# Carte_Alim_TOP.net
KiCad netlist of a schematic drawn in Altium Designer
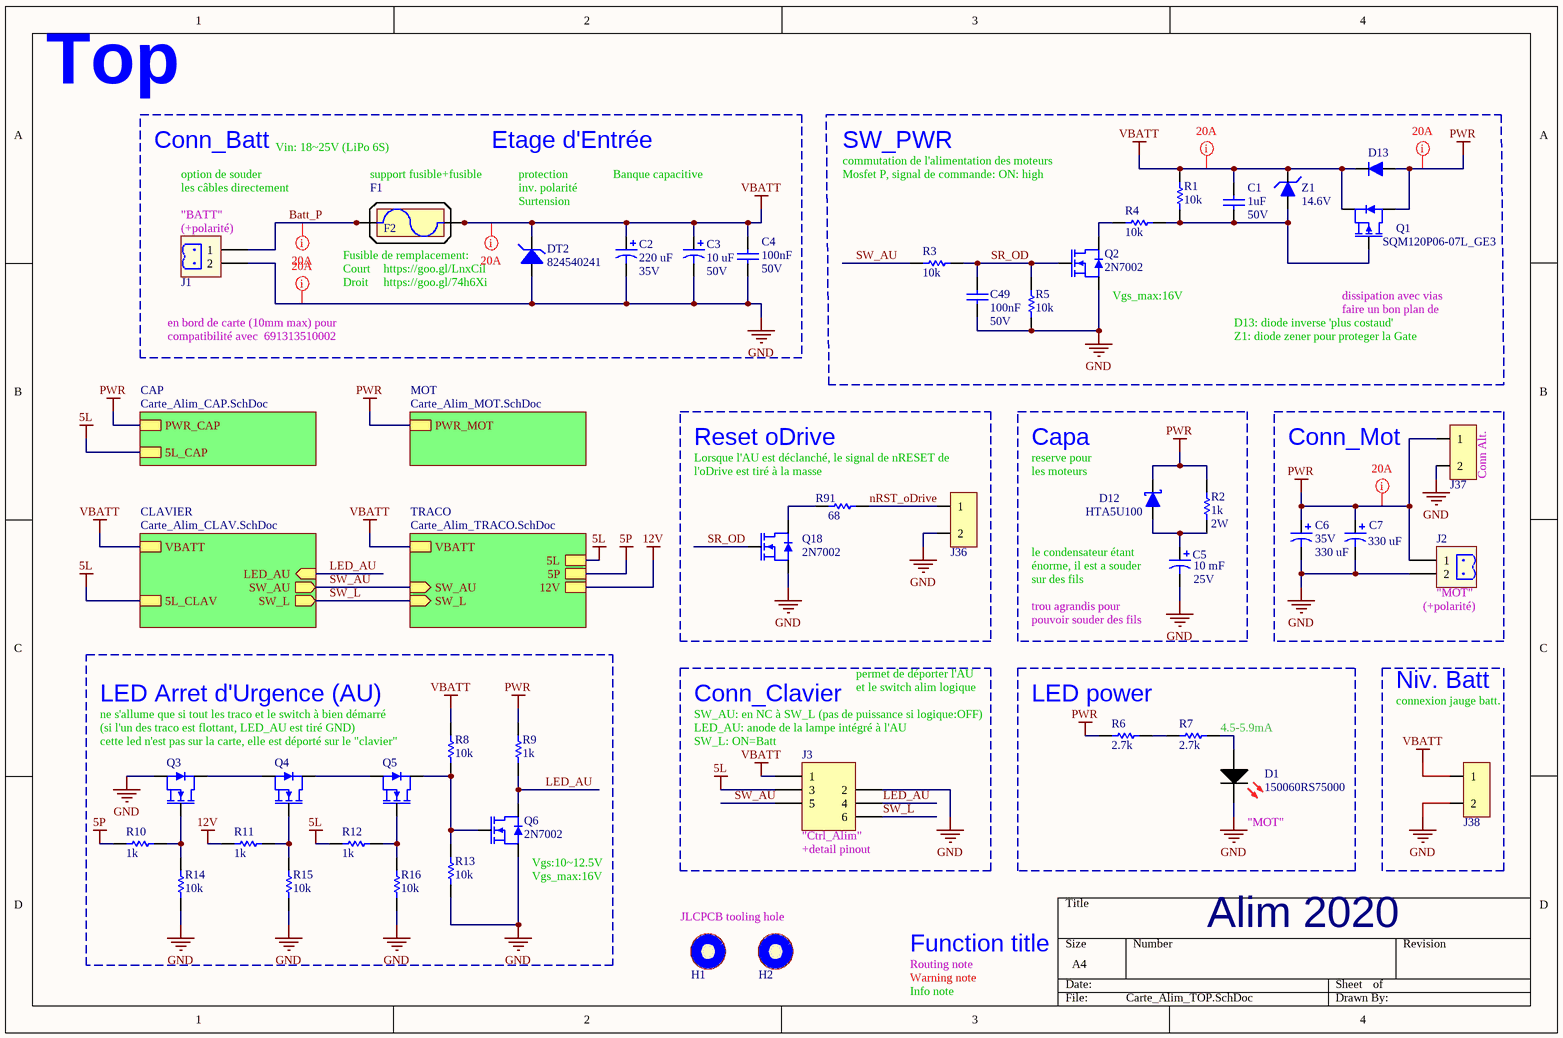
[diagram p0: Carte_Alim_TOP.SchDoc]

(export (version "E")
  (design (tool "Eeschema 10.0.6"))
  (components
    (comp (ref "C1")
      (value "1uF")
      (footprint "WCAP-CSGP_0805, 2x1.25x1.25")
      (description "CAP CER 1uF 50V X7R 0805")
      (fields
        (field (name "MANUFACTURER") "Wurth Elektronik")
        (field (name "MANUFACTURER PART NUMBER") "885012207103")
        (field (name "RATEDVOLTAGE") "50V")
      )
      (libsource (lib "Condensateur") (part "WCAP-CSGP, 885012207103"))
    )
    (comp (ref "C2")
      (value "220 uF")
      (footprint "WCAP-ATG8_8x11.5x3.5x0.5")
      (description "CAP Alu 220 UF 20% 35 V")
      (fields
        (field (name "MANUFACTURER") "Wurth Elektronik")
        (field (name "MANUFACTURER PART NUMBER") "860010574011")
        (field (name "RATEDVOLTAGE") "35V")
      )
      (libsource (lib "Condensateur") (part "WCAP-ATG8, 860010574011"))
    )
    (comp (ref "C3")
      (value "10 uF")
      (footprint "WCAP-ATG8_5x11x2x0.5")
      (description "CAP Alu 10 UF 20% 50 V")
      (fields
        (field (name "RATEDVOLTAGE") "50V")
        (field (name "MANUFACTURER") "Wurth Elektronik")
        (field (name "MANUFACTURER PART NUMBER") "860010672009")
      )
      (libsource (lib "Condensateur") (part "WCAP-ATG8, 860010672009"))
    )
    (comp (ref "C4")
      (value "100nF")
      (footprint "WCAP-CSGP_0603, 1.6x0.8x0.8")
      (description "CAP CER 100nF 50V X7R 0603")
      (fields
        (field (name "RATEDVOLTAGE") "50V")
        (field (name "MANUFACTURER") "Wurth Elektronik")
        (field (name "MANUFACTURER PART NUMBER") "885012206095")
      )
      (libsource (lib "Condensateur") (part "WCAP-CSGP, 885012206095"))
    )
    (comp (ref "C5")
      (value "10 mF")
      (footprint "WCAP-ATG8_22x41x10x0.8")
      (description "CAP Alu 10'000 UF 25 V")
      (fields
        (field (name "MANUFACTURER PART NUMBER") "860010483029")
        (field (name "MANUFACTURER") "Wurth Elektronik")
        (field (name "RATEDVOLTAGE") "25V")
      )
      (libsource (lib "Condensateur") (part "WCAP-ATG8, 860010483029"))
    )
    (comp (ref "C6")
      (value "330 uF")
      (footprint "WCAP-ATG8_10x12.5x5x0.6")
      (description "CAP Alu 330 UF 20% 35 V")
      (fields
        (field (name "MANUFACTURER") "Wurth Elektronik")
        (field (name "MANUFACTURER PART NUMBER") "860010575012")
        (field (name "RATEDVOLTAGE") "35V")
      )
      (libsource (lib "Condensateur") (part "WCAP-ATG8, 860010575012"))
    )
    (comp (ref "C7")
      (value "330 uF")
      (footprint "WCAP-ATG8_10x12.5x5x0.6")
      (description "CAP Alu 330 UF 20% 35 V")
      (fields
        (field (name "MANUFACTURER") "Wurth Elektronik")
        (field (name "MANUFACTURER PART NUMBER") "860010575012")
      )
      (libsource (lib "Condensateur") (part "WCAP-ATG8, 860010575012"))
    )
    (comp (ref "C49")
      (value "100nF")
      (footprint "WCAP-CSGP_0603, 1.6x0.8x0.8")
      (description "CAP CER 100nF 50V X7R 0603")
      (fields
        (field (name "RATEDVOLTAGE") "50V")
        (field (name "MANUFACTURER") "Wurth Elektronik")
        (field (name "MANUFACTURER PART NUMBER") "885012206095")
      )
      (libsource (lib "Condensateur") (part "WCAP-CSGP, 885012206095"))
    )
    (comp (ref "D1")
      (value "150060RS75000")
      (footprint "SMCW_0603")
      (description "SMD mono-color Chip LED, WL-SMCW, Red")
      (fields (field (name "MANUFACTURER") "Wurth Elektronik"))
      (libsource (lib "Opto") (part "WL-SMCW 0603  150060RS75000"))
    )
    (comp (ref "D12")
      (value "HTA5U100")
      (footprint "SMA, DO-214AC")
      (description "DIODE SCHOTTKY 100V 5A SMA (DO-214AC)")
      (fields (field (name "MANUFACTURER") "MULTICOMP"))
      (libsource (lib "Diode") (part "HTA5U100"))
    )
    (comp (ref "D13")
      (value "RS3J R6")
      (footprint "SMC, DO-214AB")
      (description "DIODE GEN PURP 600V 3A SMC")
      (fields (field (name "MANUFACTURER") "TAIWAN SEMICONDUCTOR"))
      (libsource (lib "Diode") (part "RS3J_R6"))
    )
    (comp (ref "DT2")
      (value "824540241")
      (footprint "SMC, DO-214AB")
      (description "WE-TVSP Power TVS Diode, Unidirectional, 1500 W, 24 VDC")
      (fields (field (name "MANUFACTURER") "Wurth Electronics Inc."))
      (libsource (lib "Diode") (part "824540241"))
    )
    (comp (ref "F1")
      (value "3557-2")
      (footprint "3557-2")
      (description "FUSE Holder 500V 30A PCB")
      (fields (field (name "MANUFACTURER") "Keystone Electronics"))
      (libsource (lib "Fuse") (part "3557-2"))
    )
    (comp (ref "F2")
      (value "0891030.NXS")
      (description "FUSE AUTO 30A 58VDC BLADE MINI")
      (fields (field (name "MANUFACTURER") "Littelfuse Inc."))
      (libsource (lib "Fuse") (part "0891030.NXS"))
    )
    (comp (ref "H1")
      (value "1.152mm")
      (footprint "Tooling_hole_JLCPCB")
      (description "Tooling hole pour JLCPCB assembly")
      (libsource (lib "Divers") (part "HOLE_TOOLING"))
    )
    (comp (ref "H2")
      (value "1.152mm")
      (footprint "Tooling_hole_JLCPCB")
      (description "Tooling hole pour JLCPCB assembly")
      (libsource (lib "Divers") (part "HOLE_TOOLING"))
    )
    (comp (ref "J1")
      (value "691311500102")
      (footprint "691311500102")
      (description "WR-TBL 2p Series 311 - 5.08 mm Closed Vertical PCB Header")
      (fields (field (name "MANUFACTURER") "Wurth Electronics Inc."))
      (libsource (lib "Connecteurs") (part "691311500102"))
    )
    (comp (ref "J2")
      (value "691311500102")
      (footprint "691311500102")
      (description "WR-TBL 2p Series 311 - 5.08 mm Closed Vertical PCB Header")
      (fields (field (name "MANUFACTURER") "Wurth Electronics Inc."))
      (libsource (lib "") (part "691311500102_1"))
    )
    (comp (ref "J3")
      (value "690367280676")
      (footprint "690367280676")
      (description "WR-MM 6p Female SMT Connector with Polarization")
      (fields (field (name "MANUFACTURER") "Wurth Electronics Inc."))
      (libsource (lib "Connecteurs") (part "690367280676"))
    )
    (comp (ref "J36")
      (value "22-03-2021")
      (footprint "22-03-2021")
      (description "CONN HEADER VERT 2POS 2.54MM")
      (fields (field (name "MANUFACTURER") "MOLEX"))
      (libsource (lib "Connecteurs") (part "22-03-2021"))
    )
    (comp (ref "J37")
      (value "22-03-2021")
      (footprint "22-03-2021")
      (description "CONN HEADER VERT 2POS 2.54MM")
      (fields (field (name "MANUFACTURER") "MOLEX"))
      (libsource (lib "Connecteurs") (part "22-03-2021"))
    )
    (comp (ref "J38")
      (value "22-03-2021")
      (footprint "22-03-2021")
      (description "CONN HEADER VERT 2POS 2.54MM")
      (fields (field (name "MANUFACTURER") "MOLEX"))
      (libsource (lib "Connecteurs") (part "22-03-2021"))
    )
    (comp (ref "Q1")
      (value "SQM120P06-07L_GE3")
      (footprint "TO263AB, D2PAK")
      (description "MOSFET P 60V 120A D2PAK")
      (fields (field (name "MANUFACTURER") "VISHAY"))
      (libsource (lib "Transistors") (part "SQM120P06-07L_GE3"))
    )
    (comp (ref "Q2")
      (value "2N7002")
      (footprint "SOT-23")
      (description "MOSFET N 60V 115MA SOT23")
      (fields (field (name "MANUFACTURER") "Changjiang Electronics Tech (CJ)"))
      (libsource (lib "Transistors") (part "2N7002"))
    )
    (comp (ref "Q3")
      (value "2N7002")
      (footprint "SOT-23")
      (description "MOSFET N 60V 115MA SOT23")
      (fields (field (name "MANUFACTURER") "Changjiang Electronics Tech (CJ)"))
      (libsource (lib "Transistors") (part "2N7002"))
    )
    (comp (ref "Q4")
      (value "2N7002")
      (footprint "SOT-23")
      (description "MOSFET N 60V 115MA SOT23")
      (fields (field (name "MANUFACTURER") "Changjiang Electronics Tech (CJ)"))
      (libsource (lib "Transistors") (part "2N7002"))
    )
    (comp (ref "Q5")
      (value "2N7002")
      (footprint "SOT-23")
      (description "MOSFET N 60V 115MA SOT23")
      (fields (field (name "MANUFACTURER") "Changjiang Electronics Tech (CJ)"))
      (libsource (lib "Transistors") (part "2N7002"))
    )
    (comp (ref "Q6")
      (value "2N7002")
      (footprint "SOT-23")
      (description "MOSFET N 60V 115MA SOT23")
      (fields (field (name "MANUFACTURER") "Changjiang Electronics Tech (CJ)"))
      (libsource (lib "Transistors") (part "2N7002"))
    )
    (comp (ref "Q18")
      (value "2N7002")
      (footprint "SOT-23")
      (description "MOSFET N 60V 115MA SOT23")
      (fields (field (name "MANUFACTURER") "Changjiang Electronics Tech (CJ)"))
      (libsource (lib "Transistors") (part "2N7002"))
    )
    (comp (ref "R1")
      (value "10k")
      (footprint "RESC1608X06N")
      (description "RES SMD 10K OHM 1% 1/10W 0603")
      (fields
        (field (name "MANUFACTURER") "Yageo")
        (field (name "MANUFACTURER PART NUMBER") "RC0603FR-0710KL")
      )
      (libsource (lib "Resistance") (part "RC0603FR-0710KL"))
    )
    (comp (ref "R2")
      (value "1k")
      (footprint "RESADV480W80L1200D390")
      (description "resistance traversante verticale générique")
      (fields
        (field (name "MANUFACTURER") "MULTICOMP")
        (field (name "MANUFACTURER PART NUMBER") "MCKNP02WJ0102A19")
        (field (name "POWER") "2W")
      )
      (libsource (lib "Resistance") (part "Generic_TH_Vert_Res"))
    )
    (comp (ref "R3")
      (value "10k")
      (footprint "RESC1608X06N")
      (description "RES SMD 10K OHM 1% 1/10W 0603")
      (fields
        (field (name "MANUFACTURER") "Yageo")
        (field (name "MANUFACTURER PART NUMBER") "RC0603FR-0710KL")
      )
      (libsource (lib "Resistance") (part "RC0603FR-0710KL"))
    )
    (comp (ref "R4")
      (value "10k")
      (footprint "RESC1608X06N")
      (description "RES SMD 10K OHM 1% 1/10W 0603")
      (fields
        (field (name "MANUFACTURER") "Yageo")
        (field (name "MANUFACTURER PART NUMBER") "RC0603FR-0710KL")
      )
      (libsource (lib "Resistance") (part "RC0603FR-0710KL"))
    )
    (comp (ref "R5")
      (value "10k")
      (footprint "RESC1608X06N")
      (description "RES SMD 10K OHM 1% 1/10W 0603")
      (fields
        (field (name "MANUFACTURER") "Yageo")
        (field (name "MANUFACTURER PART NUMBER") "RC0603FR-0710KL")
      )
      (libsource (lib "Resistance") (part "RC0603FR-0710KL"))
    )
    (comp (ref "R6")
      (value "2.7k")
      (footprint "RESC2012X06N")
      (description "RES SMD 2K7 OHM 1% 1/8W 0805")
      (fields
        (field (name "MANUFACTURER") "Yageo")
        (field (name "MANUFACTURER PART NUMBER") "RC0805FR-072K7L")
      )
      (libsource (lib "Resistance") (part "RC0805FR-072K7L"))
    )
    (comp (ref "R7")
      (value "2.7k")
      (footprint "RESC2012X06N")
      (description "RES SMD 2K7 OHM 1% 1/8W 0805")
      (fields
        (field (name "MANUFACTURER") "Yageo")
        (field (name "MANUFACTURER PART NUMBER") "RC0805FR-072K7L")
      )
      (libsource (lib "Resistance") (part "RC0805FR-072K7L"))
    )
    (comp (ref "R8")
      (value "10k")
      (footprint "RESC1608X06N")
      (description "RES SMD 10K OHM 1% 1/10W 0603")
      (fields
        (field (name "MANUFACTURER") "Yageo")
        (field (name "MANUFACTURER PART NUMBER") "RC0603FR-0710KL")
      )
      (libsource (lib "Resistance") (part "RC0603FR-0710KL"))
    )
    (comp (ref "R9")
      (value "1k")
      (footprint "RESC1608X06N")
      (description "RES SMD 1K OHM 1% 1/10W 0603")
      (fields
        (field (name "MANUFACTURER") "Yageo")
        (field (name "MANUFACTURER PART NUMBER") "RC0603FR-071KL")
      )
      (libsource (lib "Resistance") (part "RC0603FR-071KL"))
    )
    (comp (ref "R10")
      (value "1k")
      (footprint "RESC1608X06N")
      (description "RES SMD 1K OHM 1% 1/10W 0603")
      (fields
        (field (name "MANUFACTURER") "Yageo")
        (field (name "MANUFACTURER PART NUMBER") "RC0603FR-071KL")
      )
      (libsource (lib "Resistance") (part "RC0603FR-071KL"))
    )
    (comp (ref "R11")
      (value "1k")
      (footprint "RESC1608X06N")
      (description "RES SMD 1K OHM 1% 1/10W 0603")
      (fields
        (field (name "MANUFACTURER") "Yageo")
        (field (name "MANUFACTURER PART NUMBER") "RC0603FR-071KL")
      )
      (libsource (lib "Resistance") (part "RC0603FR-071KL"))
    )
    (comp (ref "R12")
      (value "1k")
      (footprint "RESC1608X06N")
      (description "RES SMD 1K OHM 1% 1/10W 0603")
      (fields
        (field (name "MANUFACTURER") "Yageo")
        (field (name "MANUFACTURER PART NUMBER") "RC0603FR-071KL")
      )
      (libsource (lib "Resistance") (part "RC0603FR-071KL"))
    )
    (comp (ref "R13")
      (value "10k")
      (footprint "RESC1608X06N")
      (description "RES SMD 10K OHM 1% 1/10W 0603")
      (fields
        (field (name "MANUFACTURER") "Yageo")
        (field (name "MANUFACTURER PART NUMBER") "RC0603FR-0710KL")
      )
      (libsource (lib "Resistance") (part "RC0603FR-0710KL"))
    )
    (comp (ref "R14")
      (value "10k")
      (footprint "RESC1608X06N")
      (description "RES SMD 10K OHM 1% 1/10W 0603")
      (fields
        (field (name "MANUFACTURER") "Yageo")
        (field (name "MANUFACTURER PART NUMBER") "RC0603FR-0710KL")
      )
      (libsource (lib "Resistance") (part "RC0603FR-0710KL"))
    )
    (comp (ref "R15")
      (value "10k")
      (footprint "RESC1608X06N")
      (description "RES SMD 10K OHM 1% 1/10W 0603")
      (fields
        (field (name "MANUFACTURER") "Yageo")
        (field (name "MANUFACTURER PART NUMBER") "RC0603FR-0710KL")
      )
      (libsource (lib "Resistance") (part "RC0603FR-0710KL"))
    )
    (comp (ref "R16")
      (value "10k")
      (footprint "RESC1608X06N")
      (description "RES SMD 10K OHM 1% 1/10W 0603")
      (fields
        (field (name "MANUFACTURER") "Yageo")
        (field (name "MANUFACTURER PART NUMBER") "RC0603FR-0710KL")
      )
      (libsource (lib "Resistance") (part "RC0603FR-0710KL"))
    )
    (comp (ref "R91")
      (value "68")
      (footprint "RESC1608X06N")
      (description "RES SMD 68 OHM 1% 1/10W 0603")
      (fields
        (field (name "MANUFACTURER") "Yageo")
        (field (name "MANUFACTURER PART NUMBER") "RC0603FR-0768RL")
      )
      (libsource (lib "Resistance") (part "RC0603FR-0768RL"))
    )
    (comp (ref "Z1")
      (value "14.6V")
      (footprint "SOD-323")
      (description "DIODE ZENER 14.6V 300mW SOD323")
      (fields
        (field (name "MANUFACTURER") "ON Semiconductor")
        (field (name "MANUFACTURER PART NUMBER") "MM3Z15VST1G")
      )
      (libsource (lib "Diode") (part "MM3Z15VST1G"))
    )
  )
  (nets
    (net (code "1") (name "/Batt_P") (class "Default")
      (node (ref "F1") (pin "1") (pinfunction "1_1") (pintype "passive"))
      (node (ref "F1") (pin "3") (pinfunction "3_3") (pintype "passive"))
      (node (ref "J1") (pin "1") (pinfunction "1_1") (pintype "passive"))
    )
    (net (code "2") (name "/LED_AU") (class "Default")
      (node (ref "J3") (pin "4") (pinfunction "4_4") (pintype "passive"))
      (node (ref "Q6") (pin "3") (pinfunction "D_3") (pintype "passive"))
      (node (ref "R9") (pin "1") (pinfunction "1_1") (pintype "passive"))
    )
    (net (code "3") (name "/SR_OD") (class "Default")
      (node (ref "C49") (pin "2") (pinfunction "2_2") (pintype "passive"))
      (node (ref "Q18") (pin "1") (pinfunction "G_1") (pintype "passive"))
      (node (ref "Q2") (pin "1") (pinfunction "G_1") (pintype "passive"))
      (node (ref "R3") (pin "2") (pinfunction "2_2") (pintype "passive"))
      (node (ref "R5") (pin "1") (pinfunction "1_1") (pintype "passive"))
    )
    (net (code "4") (name "/SW_AU") (class "Default")
      (node (ref "J3") (pin "5") (pinfunction "5_5") (pintype "passive"))
      (node (ref "R3") (pin "1") (pinfunction "1_1") (pintype "passive"))
    )
    (net (code "5") (name "/SW_L") (class "Default")
      (node (ref "J3") (pin "6") (pinfunction "6_6") (pintype "passive"))
    )
    (net (code "6") (name "/nRST_oDrive") (class "Default")
      (node (ref "J36") (pin "1") (pinfunction "1_1") (pintype "passive"))
      (node (ref "R91") (pin "2") (pinfunction "2_2") (pintype "passive"))
    )
    (net (code "7") (name "5L") (class "Default")
      (node (ref "J3") (pin "3") (pinfunction "3_3") (pintype "passive"))
      (node (ref "R12") (pin "2") (pinfunction "2_2") (pintype "passive"))
    )
    (net (code "8") (name "5P") (class "Default")
      (node (ref "R10") (pin "2") (pinfunction "2_2") (pintype "passive"))
    )
    (net (code "9") (name "12V") (class "Default")
      (node (ref "R11") (pin "2") (pinfunction "2_2") (pintype "passive"))
    )
    (net (code "10") (name "GND") (class "Default")
      (node (ref "C2") (pin "2") (pinfunction "2_2") (pintype "passive"))
      (node (ref "C3") (pin "2") (pinfunction "2_2") (pintype "passive"))
      (node (ref "C4") (pin "1") (pinfunction "1_1") (pintype "passive"))
      (node (ref "C49") (pin "1") (pinfunction "1_1") (pintype "passive"))
      (node (ref "C5") (pin "2") (pinfunction "2_2") (pintype "passive"))
      (node (ref "C6") (pin "2") (pinfunction "2_2") (pintype "passive"))
      (node (ref "C7") (pin "2") (pinfunction "2_2") (pintype "passive"))
      (node (ref "D1") (pin "1") (pinfunction "C_1") (pintype "passive"))
      (node (ref "DT2") (pin "1") (pintype "passive"))
      (node (ref "J1") (pin "2") (pinfunction "2_2") (pintype "passive"))
      (node (ref "J2") (pin "2") (pinfunction "2_2") (pintype "passive"))
      (node (ref "J3") (pin "2") (pinfunction "2_2") (pintype "passive"))
      (node (ref "J36") (pin "2") (pinfunction "2_2") (pintype "passive"))
      (node (ref "J37") (pin "2") (pinfunction "2_2") (pintype "passive"))
      (node (ref "J38") (pin "2") (pinfunction "2_2") (pintype "passive"))
      (node (ref "Q18") (pin "2") (pinfunction "S_2") (pintype "passive"))
      (node (ref "Q2") (pin "2") (pinfunction "S_2") (pintype "passive"))
      (node (ref "Q3") (pin "2") (pinfunction "S_2") (pintype "passive"))
      (node (ref "Q6") (pin "2") (pinfunction "S_2") (pintype "passive"))
      (node (ref "R13") (pin "1") (pinfunction "1_1") (pintype "passive"))
      (node (ref "R14") (pin "1") (pinfunction "1_1") (pintype "passive"))
      (node (ref "R15") (pin "1") (pinfunction "1_1") (pintype "passive"))
      (node (ref "R16") (pin "1") (pinfunction "1_1") (pintype "passive"))
      (node (ref "R5") (pin "2") (pinfunction "2_2") (pintype "passive"))
    )
    (net (code "11") (name "Net-(C5-Pad1)") (class "Default")
      (node (ref "C5") (pin "1") (pinfunction "1_1") (pintype "passive"))
      (node (ref "D12") (pin "1") (pintype "passive"))
      (node (ref "R2") (pin "2") (pinfunction "2_2") (pintype "passive"))
    )
    (net (code "12") (name "Net-(D1-A)") (class "Default")
      (node (ref "D1") (pin "2") (pinfunction "A_2") (pintype "passive"))
      (node (ref "R7") (pin "1") (pinfunction "1_1") (pintype "passive"))
    )
    (net (code "13") (name "Net-(Q1-G)") (class "Default")
      (node (ref "C1") (pin "1") (pinfunction "1_1") (pintype "passive"))
      (node (ref "Q1") (pin "1") (pinfunction "G_1") (pintype "passive"))
      (node (ref "R1") (pin "1") (pinfunction "1_1") (pintype "passive"))
      (node (ref "R4") (pin "1") (pinfunction "1_1") (pintype "passive"))
      (node (ref "Z1") (pin "1") (pintype "passive"))
    )
    (net (code "14") (name "Net-(Q2-D)") (class "Default")
      (node (ref "Q2") (pin "3") (pinfunction "D_3") (pintype "passive"))
      (node (ref "R4") (pin "2") (pinfunction "2_2") (pintype "passive"))
    )
    (net (code "15") (name "Net-(Q3-D)") (class "Default")
      (node (ref "Q3") (pin "3") (pinfunction "D_3") (pintype "passive"))
      (node (ref "Q4") (pin "2") (pinfunction "S_2") (pintype "passive"))
    )
    (net (code "16") (name "Net-(Q3-G)") (class "Default")
      (node (ref "Q3") (pin "1") (pinfunction "G_1") (pintype "passive"))
      (node (ref "R10") (pin "1") (pinfunction "1_1") (pintype "passive"))
      (node (ref "R14") (pin "2") (pinfunction "2_2") (pintype "passive"))
    )
    (net (code "17") (name "Net-(Q4-D)") (class "Default")
      (node (ref "Q4") (pin "3") (pinfunction "D_3") (pintype "passive"))
      (node (ref "Q5") (pin "2") (pinfunction "S_2") (pintype "passive"))
    )
    (net (code "18") (name "Net-(Q4-G)") (class "Default")
      (node (ref "Q4") (pin "1") (pinfunction "G_1") (pintype "passive"))
      (node (ref "R11") (pin "1") (pinfunction "1_1") (pintype "passive"))
      (node (ref "R15") (pin "2") (pinfunction "2_2") (pintype "passive"))
    )
    (net (code "19") (name "Net-(Q5-D)") (class "Default")
      (node (ref "Q5") (pin "3") (pinfunction "D_3") (pintype "passive"))
      (node (ref "Q6") (pin "1") (pinfunction "G_1") (pintype "passive"))
      (node (ref "R13") (pin "2") (pinfunction "2_2") (pintype "passive"))
      (node (ref "R8") (pin "1") (pinfunction "1_1") (pintype "passive"))
    )
    (net (code "20") (name "Net-(Q5-G)") (class "Default")
      (node (ref "Q5") (pin "1") (pinfunction "G_1") (pintype "passive"))
      (node (ref "R12") (pin "1") (pinfunction "1_1") (pintype "passive"))
      (node (ref "R16") (pin "2") (pinfunction "2_2") (pintype "passive"))
    )
    (net (code "21") (name "Net-(Q18-D)") (class "Default")
      (node (ref "Q18") (pin "3") (pinfunction "D_3") (pintype "passive"))
      (node (ref "R91") (pin "1") (pinfunction "1_1") (pintype "passive"))
    )
    (net (code "22") (name "Net-(R6-Pad2)") (class "Default")
      (node (ref "R6") (pin "2") (pinfunction "2_2") (pintype "passive"))
      (node (ref "R7") (pin "2") (pinfunction "2_2") (pintype "passive"))
    )
    (net (code "23") (name "PWR") (class "Default")
      (node (ref "C6") (pin "1") (pinfunction "1_1") (pintype "passive"))
      (node (ref "C7") (pin "1") (pinfunction "1_1") (pintype "passive"))
      (node (ref "D12") (pin "2") (pintype "passive"))
      (node (ref "D13") (pin "1") (pintype "passive"))
      (node (ref "J2") (pin "1") (pinfunction "1_1") (pintype "passive"))
      (node (ref "J37") (pin "1") (pinfunction "1_1") (pintype "passive"))
      (node (ref "Q1") (pin "4") (pinfunction "D_4") (pintype "passive"))
      (node (ref "R2") (pin "1") (pinfunction "1_1") (pintype "passive"))
      (node (ref "R6") (pin "1") (pinfunction "1_1") (pintype "passive"))
      (node (ref "R9") (pin "2") (pinfunction "2_2") (pintype "passive"))
    )
    (net (code "24") (name "VBATT") (class "Default")
      (node (ref "C1") (pin "2") (pinfunction "2_2") (pintype "passive"))
      (node (ref "C2") (pin "1") (pinfunction "1_1") (pintype "passive"))
      (node (ref "C3") (pin "1") (pinfunction "1_1") (pintype "passive"))
      (node (ref "C4") (pin "2") (pinfunction "2_2") (pintype "passive"))
      (node (ref "D13") (pin "2") (pintype "passive"))
      (node (ref "DT2") (pin "2") (pintype "passive"))
      (node (ref "F1") (pin "2") (pinfunction "2_2") (pintype "passive"))
      (node (ref "F1") (pin "4") (pinfunction "4_4") (pintype "passive"))
      (node (ref "J3") (pin "1") (pinfunction "1_1") (pintype "passive"))
      (node (ref "J38") (pin "1") (pinfunction "1_1") (pintype "passive"))
      (node (ref "Q1") (pin "3") (pinfunction "S_3") (pintype "passive"))
      (node (ref "R1") (pin "2") (pinfunction "2_2") (pintype "passive"))
      (node (ref "R8") (pin "2") (pinfunction "2_2") (pintype "passive"))
      (node (ref "Z1") (pin "2") (pintype "passive"))
    )
  )
)
